# esp32_r1.net
KiCad netlist of a schematic drawn in EAGLE
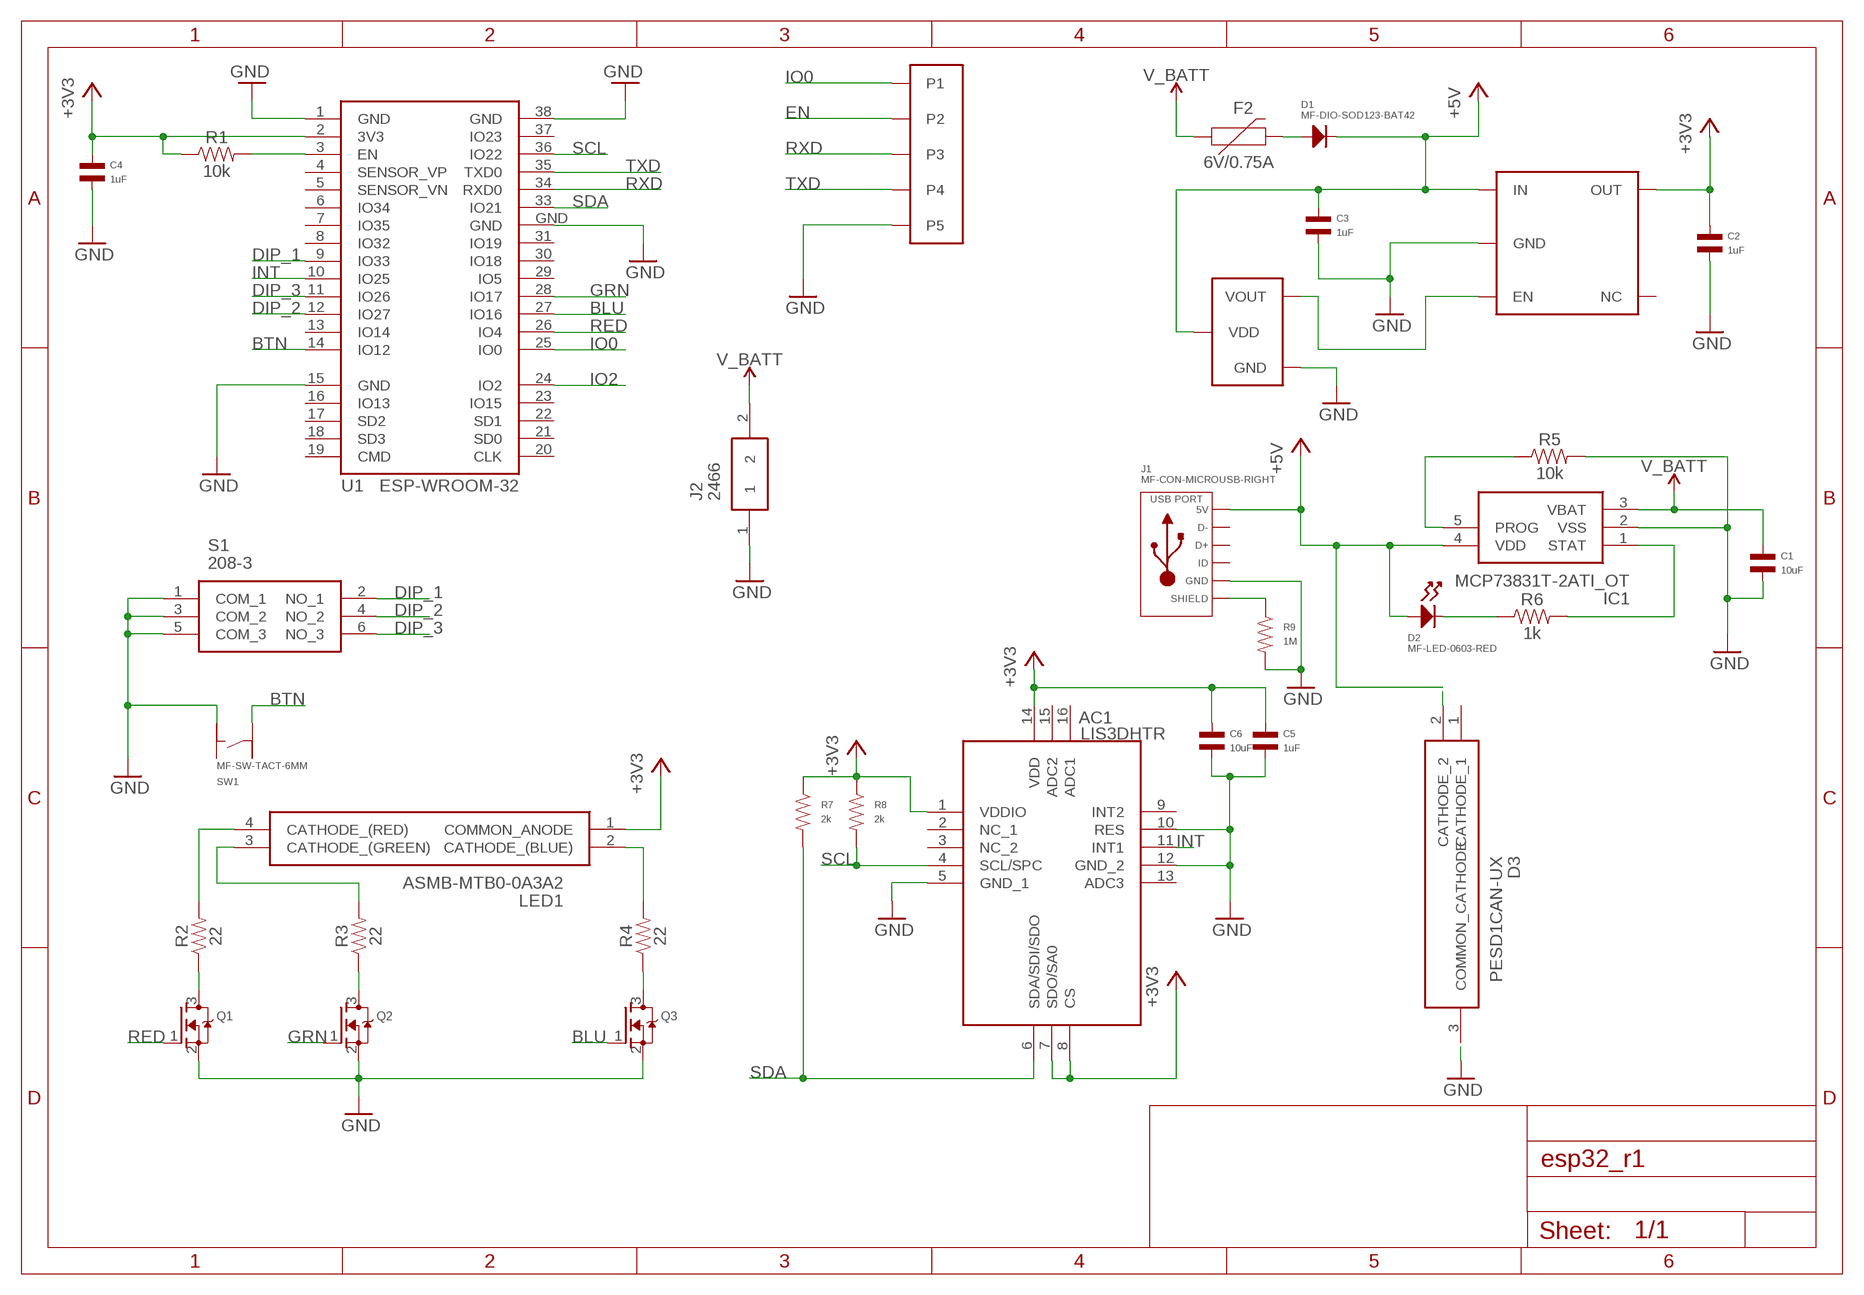
[diagram p0: schematic, sheet 1]

(export (version "E")
  (design (tool "Eeschema 10.0.6"))
  (components
    (comp (ref "AC1")
      (value "LIS3DHTR")
      (footprint "eagle-import:PQFN50P300X300X100-16N")
      (fields (field (name "MOUSER_PART_NUMBER") "511-LIS3DHTR") (field (name "RS_PART_NUMBER") "7931364P"))
      (libsource (lib "eagle-import") (part "LIS3DHTR"))
    )
    (comp (ref "C1")
      (value "10uF")
      (footprint "eagle-import:C1206")
      (libsource (lib "eagle-import") (part "CAPACITOR_NP_1206"))
    )
    (comp (ref "C2")
      (value "1uF")
      (footprint "eagle-import:C0402")
      (libsource (lib "eagle-import") (part "CAPACITOR_NP_0402"))
    )
    (comp (ref "C3")
      (value "1uF")
      (footprint "eagle-import:C0402")
      (libsource (lib "eagle-import") (part "CAPACITOR_NP_0402"))
    )
    (comp (ref "C4")
      (value "1uF")
      (footprint "eagle-import:C0402")
      (libsource (lib "eagle-import") (part "CAPACITOR_NP_0402"))
    )
    (comp (ref "C5")
      (value "1uF")
      (footprint "eagle-import:C0402")
      (libsource (lib "eagle-import") (part "CAPACITOR_NP_0402"))
    )
    (comp (ref "C6")
      (value "10uF")
      (footprint "eagle-import:C1206")
      (libsource (lib "eagle-import") (part "CAPACITOR_NP_1206"))
    )
    (comp (ref "D1")
      (value "MF-DIO-SOD123-BAT42")
      (footprint "eagle-import:SOD-123")
      (fields (field (name "HOUSEPART") "YES"))
      (libsource (lib "eagle-import") (part "DIODES_SOD-123_BAT42"))
    )
    (comp (ref "D2")
      (value "MF-LED-0603-RED")
      (footprint "eagle-import:LED0603")
      (fields (field (name "HOUSEPART") "YES"))
      (libsource (lib "eagle-import") (part "LED_SINGLE-0603-RED"))
    )
    (comp (ref "D3")
      (value "PESD1CAN-UX")
      (footprint "eagle-import:SOT95P230X110-3N")
      (fields (field (name "MOUSER_PART_NUMBER") "771-PESD1CANUX") (field (name "RS_PART_NUMBER") "1362213P"))
      (libsource (lib "eagle-import") (part "PESD1CAN-UX"))
    )
    (comp (ref "F2")
      (value "6V/0.75A")
      (footprint "eagle-import:1206")
      (libsource (lib "eagle-import") (part "PPTC_THREE-QUARTER-AMP"))
    )
    (comp (ref "IC1")
      (value "MCP73831T-2ATI_OT")
      (footprint "eagle-import:SOT95P270X145-5N")
      (fields
        (field (name "MANUFACTURER_PART_NUMBER") "MCP73831T-2ATI/OT")
        (field (name "MOUSER_PART_NUMBER") "579-MCP73831T-2ATIOT")
        (field (name "RS_PART_NUMBER") "7386617P")
      )
      (libsource (lib "eagle-import") (part "MCP73831T-2ATI_OT"))
    )
    (comp (ref "J1")
      (value "MF-CON-MICROUSB-RIGHT")
      (footprint "eagle-import:MICROUSB-RIGHT")
      (fields (field (name "HOUSEPART") "YES"))
      (libsource (lib "eagle-import") (part "USB_MICRO_RIGHT"))
    )
    (comp (ref "J2")
      (value "2466")
      (footprint "eagle-import:2466")
      (fields (field (name "MOUSER_PART_NUMBER") "534-2466"))
      (libsource (lib "eagle-import") (part "2466"))
    )
    (comp (ref "LED1")
      (value "ASMB-MTB0-0A3A2")
      (footprint "eagle-import:AVAGO_PLCC4")
      (fields
        (field (name "MOUSER_PART_NUMBER") "630-ASMB-MTB0-0A3A2")
        (field (name "RS_PART_NUMBER") "8305044P")
      )
      (libsource (lib "eagle-import") (part "ASMB-MTB0-0A3A2"))
    )
    (comp (ref "Q1")
      (value "MOSFET-NREFLOW")
      (footprint "eagle-import:SOT23-R")
      (libsource (lib "eagle-import") (part "MOSFET-NREFLOW"))
    )
    (comp (ref "Q2")
      (value "MOSFET-NREFLOW")
      (footprint "eagle-import:SOT23-R")
      (libsource (lib "eagle-import") (part "MOSFET-NREFLOW"))
    )
    (comp (ref "Q3")
      (value "MOSFET-NREFLOW")
      (footprint "eagle-import:SOT23-R")
      (libsource (lib "eagle-import") (part "MOSFET-NREFLOW"))
    )
    (comp (ref "R1")
      (value "10k")
      (footprint "eagle-import:0402")
      (libsource (lib "eagle-import") (part "100KOHM-0402-1/16W-1%"))
    )
    (comp (ref "R2")
      (value "22")
      (footprint "eagle-import:0402")
      (libsource (lib "eagle-import") (part "22OHM-0402-1/10W-1%"))
    )
    (comp (ref "R3")
      (value "22")
      (footprint "eagle-import:0402")
      (libsource (lib "eagle-import") (part "22OHM-0402-1/10W-1%"))
    )
    (comp (ref "R4")
      (value "22")
      (footprint "eagle-import:0402")
      (libsource (lib "eagle-import") (part "22OHM-0402-1/10W-1%"))
    )
    (comp (ref "R5")
      (value "10k")
      (footprint "eagle-import:0402")
      (libsource (lib "eagle-import") (part "100KOHM-0402-1/16W-1%"))
    )
    (comp (ref "R6")
      (value "1k")
      (footprint "eagle-import:0402")
      (libsource (lib "eagle-import") (part "100KOHM-0402-1/16W-1%"))
    )
    (comp (ref "R7")
      (value "2k")
      (footprint "eagle-import:R0402")
      (libsource (lib "eagle-import") (part "RESISTOR_0402"))
    )
    (comp (ref "R8")
      (value "2k")
      (footprint "eagle-import:R0402")
      (libsource (lib "eagle-import") (part "RESISTOR_0402"))
    )
    (comp (ref "R9")
      (value "1M")
      (footprint "eagle-import:R0402")
      (libsource (lib "eagle-import") (part "RESISTOR_0402"))
    )
    (comp (ref "S1")
      (value "208-3")
      (footprint "eagle-import:2083")
      (fields (field (name "MOUSER_PART_NUMBER") "774-2083") (field (name "RS_PART_NUMBER") "1774319"))
      (libsource (lib "eagle-import") (part "208-3"))
    )
    (comp (ref "SW1")
      (value "MF-SW-TACT-6MM")
      (footprint "eagle-import:TACT6MM")
      (fields (field (name "HOUSEPART") "YES"))
      (libsource (lib "eagle-import") (part "TACT_6MM"))
    )
    (comp (ref "U1")
      (value "ESP-WROOM-32")
      (footprint "eagle-import:ESP-WROOM-32")
      (libsource (lib "eagle-import") (part "ESP-WROOM-32"))
    )
    (comp (ref "U4")
      (value "TLV755")
      (footprint "eagle-import:SOT23-DBV")
      (libsource (lib "eagle-import") (part "TLV755"))
    )
    (comp (ref "U6")
      (value "53047")
      (footprint "eagle-import:PICOBLADE_53047")
      (libsource (lib "eagle-import") (part "53047"))
    )
    (comp (ref "U7")
      (value "BD49K33G")
      (footprint "eagle-import:SSOP3")
      (libsource (lib "eagle-import") (part "BD49K33G"))
    )
  )
  (nets
    (net (code "1") (name "+3V3") (class "Default")
      (node (ref "AC1") (pin "1") (pinfunction "VDDIO_1") (pintype "power_in"))
      (node (ref "AC1") (pin "14") (pinfunction "VDD_14") (pintype "power_in"))
      (node (ref "AC1") (pin "7") (pinfunction "SDO/SA0_7") (pintype "bidirectional"))
      (node (ref "AC1") (pin "8") (pinfunction "CS_8") (pintype "input"))
      (node (ref "C2") (pin "P$1") (pinfunction "P$1_P$1") (pintype "passive"))
      (node (ref "C4") (pin "P$1") (pinfunction "P$1_P$1") (pintype "passive"))
      (node (ref "C5") (pin "P$1") (pinfunction "P$1_P$1") (pintype "passive"))
      (node (ref "C6") (pin "P$1") (pinfunction "P$1_P$1") (pintype "passive"))
      (node (ref "LED1") (pin "1") (pinfunction "COMMON_ANODE_1") (pintype "bidirectional"))
      (node (ref "R1") (pin "1") (pinfunction "1_1") (pintype "passive"))
      (node (ref "R7") (pin "P$1") (pinfunction "P$1_P$1") (pintype "passive"))
      (node (ref "R8") (pin "P$1") (pinfunction "P$1_P$1") (pintype "passive"))
      (node (ref "U1") (pin "2") (pinfunction "3V3_2") (pintype "power_in"))
      (node (ref "U4") (pin "5") (pinfunction "OUT_5") (pintype "bidirectional"))
    )
    (net (code "2") (name "+5V") (class "Default")
      (node (ref "C3") (pin "P$1") (pinfunction "P$1_P$1") (pintype "passive"))
      (node (ref "D1") (pin "CATHODE") (pinfunction "CATHODE_CATHODE") (pintype "bidirectional"))
      (node (ref "D2") (pin "ANODE") (pinfunction "ANODE_ANODE") (pintype "power_in"))
      (node (ref "D3") (pin "2") (pinfunction "CATHODE_2_2") (pintype "bidirectional"))
      (node (ref "IC1") (pin "4") (pinfunction "VDD_4") (pintype "power_in"))
      (node (ref "J1") (pin "1") (pinfunction "5V_1") (pintype "power_in"))
      (node (ref "U4") (pin "1") (pinfunction "IN_1") (pintype "bidirectional"))
      (node (ref "U7") (pin "P$3") (pinfunction "VDD_P$3") (pintype "bidirectional"))
    )
    (net (code "3") (name "/BLU") (class "Default")
      (node (ref "Q3") (pin "1") (pinfunction "G_1") (pintype "bidirectional"))
      (node (ref "U1") (pin "27") (pinfunction "IO16_27") (pintype "bidirectional"))
    )
    (net (code "4") (name "/BTN") (class "Default")
      (node (ref "SW1") (pin "P$4") (pinfunction "P$4_P$4") (pintype "bidirectional"))
      (node (ref "U1") (pin "14") (pinfunction "IO12_14") (pintype "bidirectional"))
    )
    (net (code "5") (name "/DIP_1") (class "Default")
      (node (ref "S1") (pin "2") (pinfunction "NO_1_2") (pintype "bidirectional"))
      (node (ref "U1") (pin "9") (pinfunction "IO33_9") (pintype "bidirectional"))
    )
    (net (code "6") (name "/DIP_2") (class "Default")
      (node (ref "S1") (pin "4") (pinfunction "NO_2_4") (pintype "bidirectional"))
      (node (ref "U1") (pin "12") (pinfunction "IO27_12") (pintype "bidirectional"))
    )
    (net (code "7") (name "/DIP_3") (class "Default")
      (node (ref "S1") (pin "6") (pinfunction "NO_3_6") (pintype "bidirectional"))
      (node (ref "U1") (pin "11") (pinfunction "IO26_11") (pintype "bidirectional"))
    )
    (net (code "8") (name "/EN") (class "Default")
      (node (ref "R1") (pin "2") (pinfunction "2_2") (pintype "passive"))
      (node (ref "U1") (pin "3") (pinfunction "EN_3") (pintype "input"))
      (node (ref "U6") (pin "P$2") (pinfunction "P2_P$2") (pintype "bidirectional"))
    )
    (net (code "9") (name "/GRN") (class "Default")
      (node (ref "Q2") (pin "1") (pinfunction "G_1") (pintype "bidirectional"))
      (node (ref "U1") (pin "28") (pinfunction "IO17_28") (pintype "bidirectional"))
    )
    (net (code "10") (name "/INT") (class "Default")
      (node (ref "AC1") (pin "11") (pinfunction "INT1_11") (pintype "input"))
      (node (ref "U1") (pin "10") (pinfunction "IO25_10") (pintype "bidirectional"))
    )
    (net (code "11") (name "/IO0") (class "Default")
      (node (ref "U1") (pin "25") (pinfunction "IO0_25") (pintype "bidirectional"))
      (node (ref "U6") (pin "P$1") (pinfunction "P1_P$1") (pintype "bidirectional"))
    )
    (net (code "12") (name "/IO2") (class "Default")
      (node (ref "U1") (pin "24") (pinfunction "IO2_24") (pintype "bidirectional"))
    )
    (net (code "13") (name "/RED") (class "Default")
      (node (ref "Q1") (pin "1") (pinfunction "G_1") (pintype "bidirectional"))
      (node (ref "U1") (pin "26") (pinfunction "IO4_26") (pintype "bidirectional"))
    )
    (net (code "14") (name "/RXD") (class "Default")
      (node (ref "U1") (pin "34") (pinfunction "RXD0_34") (pintype "bidirectional"))
      (node (ref "U6") (pin "P$3") (pinfunction "P3_P$3") (pintype "bidirectional"))
    )
    (net (code "15") (name "/SCL") (class "Default")
      (node (ref "AC1") (pin "4") (pinfunction "SCL/SPC_4") (pintype "bidirectional"))
      (node (ref "R8") (pin "P$2") (pinfunction "P$2_P$2") (pintype "passive"))
      (node (ref "U1") (pin "36") (pinfunction "IO22_36") (pintype "bidirectional"))
    )
    (net (code "16") (name "/SDA") (class "Default")
      (node (ref "AC1") (pin "6") (pinfunction "SDA/SDI/SDO_6") (pintype "bidirectional"))
      (node (ref "R7") (pin "P$2") (pinfunction "P$2_P$2") (pintype "passive"))
      (node (ref "U1") (pin "33") (pinfunction "IO21_33") (pintype "bidirectional"))
    )
    (net (code "17") (name "/TXD") (class "Default")
      (node (ref "U1") (pin "35") (pinfunction "TXD0_35") (pintype "bidirectional"))
      (node (ref "U6") (pin "P$4") (pinfunction "P4_P$4") (pintype "bidirectional"))
    )
    (net (code "18") (name "GND") (class "Default")
      (node (ref "AC1") (pin "10") (pinfunction "RES_10") (pintype "bidirectional"))
      (node (ref "AC1") (pin "12") (pinfunction "GND_2_12") (pintype "power_in"))
      (node (ref "AC1") (pin "5") (pinfunction "GND_1_5") (pintype "power_in"))
      (node (ref "C1") (pin "P$2") (pinfunction "P$2_P$2") (pintype "passive"))
      (node (ref "C2") (pin "P$2") (pinfunction "P$2_P$2") (pintype "passive"))
      (node (ref "C3") (pin "P$2") (pinfunction "P$2_P$2") (pintype "passive"))
      (node (ref "C4") (pin "P$2") (pinfunction "P$2_P$2") (pintype "passive"))
      (node (ref "C5") (pin "P$2") (pinfunction "P$2_P$2") (pintype "passive"))
      (node (ref "C6") (pin "P$2") (pinfunction "P$2_P$2") (pintype "passive"))
      (node (ref "D3") (pin "3") (pinfunction "COMMON_CATHODE_3") (pintype "bidirectional"))
      (node (ref "IC1") (pin "2") (pinfunction "VSS_2") (pintype "power_in"))
      (node (ref "J1") (pin "5") (pinfunction "GND_5") (pintype "power_in"))
      (node (ref "J2") (pin "1") (pinfunction "1_1") (pintype "bidirectional"))
      (node (ref "Q1") (pin "2") (pinfunction "S_2") (pintype "bidirectional"))
      (node (ref "Q2") (pin "2") (pinfunction "S_2") (pintype "bidirectional"))
      (node (ref "Q3") (pin "2") (pinfunction "S_2") (pintype "bidirectional"))
      (node (ref "R5") (pin "2") (pinfunction "2_2") (pintype "passive"))
      (node (ref "R9") (pin "P$2") (pinfunction "P$2_P$2") (pintype "passive"))
      (node (ref "S1") (pin "1") (pinfunction "COM_1_1") (pintype "bidirectional"))
      (node (ref "S1") (pin "3") (pinfunction "COM_2_3") (pintype "bidirectional"))
      (node (ref "S1") (pin "5") (pinfunction "COM_3_5") (pintype "bidirectional"))
      (node (ref "SW1") (pin "P$2") (pinfunction "P$2_P$2") (pintype "bidirectional"))
      (node (ref "U1") (pin "1") (pinfunction "GND_1") (pintype "power_in"))
      (node (ref "U1") (pin "15") (pinfunction "GND_15") (pintype "power_in"))
      (node (ref "U1") (pin "38") (pinfunction "GND_38") (pintype "power_in"))
      (node (ref "U1") (pin "GND") (pinfunction "GND_GND") (pintype "power_in"))
      (node (ref "U4") (pin "2") (pinfunction "GND_2") (pintype "bidirectional"))
      (node (ref "U6") (pin "P$5") (pinfunction "P5_P$5") (pintype "bidirectional"))
      (node (ref "U7") (pin "P$1") (pinfunction "GND_P$1") (pintype "bidirectional"))
    )
    (net (code "19") (name "Net-(D1-PadANODE)") (class "Default")
      (node (ref "D1") (pin "ANODE") (pinfunction "ANODE_ANODE") (pintype "bidirectional"))
      (node (ref "F2") (pin "2") (pinfunction "2_2") (pintype "bidirectional"))
    )
    (net (code "20") (name "Net-(D2-PadCATHODE)") (class "Default")
      (node (ref "D2") (pin "CATHODE") (pinfunction "CATHODE_CATHODE") (pintype "power_in"))
      (node (ref "R6") (pin "1") (pinfunction "1_1") (pintype "passive"))
    )
    (net (code "21") (name "Net-(IC1-PROG)") (class "Default")
      (node (ref "IC1") (pin "5") (pinfunction "PROG_5") (pintype "bidirectional"))
      (node (ref "R5") (pin "1") (pinfunction "1_1") (pintype "passive"))
    )
    (net (code "22") (name "Net-(IC1-STAT)") (class "Default")
      (node (ref "IC1") (pin "1") (pinfunction "STAT_1") (pintype "bidirectional"))
      (node (ref "R6") (pin "2") (pinfunction "2_2") (pintype "passive"))
    )
    (net (code "23") (name "Net-(J1-SLD-PadS1)") (class "Default")
      (node (ref "J1") (pin "S1") (pinfunction "SLD_S1") (pintype "power_in"))
      (node (ref "J1") (pin "S2") (pinfunction "SLD_S2") (pintype "power_in"))
      (node (ref "J1") (pin "S3") (pinfunction "SLD_S3") (pintype "power_in"))
      (node (ref "J1") (pin "S4") (pinfunction "SLD_S4") (pintype "power_in"))
      (node (ref "J1") (pin "S5") (pinfunction "SLD_S5") (pintype "power_in"))
      (node (ref "J1") (pin "S6") (pinfunction "SLD_S6") (pintype "power_in"))
      (node (ref "R9") (pin "P$1") (pinfunction "P$1_P$1") (pintype "passive"))
    )
    (net (code "24") (name "Net-(LED1-CATHODE_(BLUE))") (class "Default")
      (node (ref "LED1") (pin "2") (pinfunction "CATHODE_(BLUE)_2") (pintype "bidirectional"))
      (node (ref "R4") (pin "2") (pinfunction "2_2") (pintype "passive"))
    )
    (net (code "25") (name "Net-(LED1-CATHODE_(GREEN))") (class "Default")
      (node (ref "LED1") (pin "3") (pinfunction "CATHODE_(GREEN)_3") (pintype "bidirectional"))
      (node (ref "R3") (pin "2") (pinfunction "2_2") (pintype "passive"))
    )
    (net (code "26") (name "Net-(LED1-CATHODE_(RED))") (class "Default")
      (node (ref "LED1") (pin "4") (pinfunction "CATHODE_(RED)_4") (pintype "bidirectional"))
      (node (ref "R2") (pin "2") (pinfunction "2_2") (pintype "passive"))
    )
    (net (code "27") (name "Net-(Q1-D)") (class "Default")
      (node (ref "Q1") (pin "3") (pinfunction "D_3") (pintype "bidirectional"))
      (node (ref "R2") (pin "1") (pinfunction "1_1") (pintype "passive"))
    )
    (net (code "28") (name "Net-(Q2-D)") (class "Default")
      (node (ref "Q2") (pin "3") (pinfunction "D_3") (pintype "bidirectional"))
      (node (ref "R3") (pin "1") (pinfunction "1_1") (pintype "passive"))
    )
    (net (code "29") (name "Net-(Q3-D)") (class "Default")
      (node (ref "Q3") (pin "3") (pinfunction "D_3") (pintype "bidirectional"))
      (node (ref "R4") (pin "1") (pinfunction "1_1") (pintype "passive"))
    )
    (net (code "30") (name "Net-(U4-EN)") (class "Default")
      (node (ref "U4") (pin "3") (pinfunction "EN_3") (pintype "bidirectional"))
      (node (ref "U7") (pin "P$2") (pinfunction "VOUT_P$2") (pintype "bidirectional"))
    )
    (net (code "31") (name "V_BATT") (class "Default")
      (node (ref "C1") (pin "P$1") (pinfunction "P$1_P$1") (pintype "passive"))
      (node (ref "F2") (pin "1") (pinfunction "1_1") (pintype "bidirectional"))
      (node (ref "IC1") (pin "3") (pinfunction "VBAT_3") (pintype "bidirectional"))
      (node (ref "J2") (pin "2") (pinfunction "2_2") (pintype "bidirectional"))
    )
    (net (code "32") (name "unconnected-(AC1-ADC1-Pad16)") (class "Default")
      (node (ref "AC1") (pin "16") (pinfunction "ADC1_16") (pintype "bidirectional"))
    )
    (net (code "33") (name "unconnected-(AC1-ADC2-Pad15)") (class "Default")
      (node (ref "AC1") (pin "15") (pinfunction "ADC2_15") (pintype "bidirectional"))
    )
    (net (code "34") (name "unconnected-(AC1-ADC3-Pad13)") (class "Default")
      (node (ref "AC1") (pin "13") (pinfunction "ADC3_13") (pintype "bidirectional"))
    )
    (net (code "35") (name "unconnected-(AC1-INT2-Pad9)") (class "Default")
      (node (ref "AC1") (pin "9") (pinfunction "INT2_9") (pintype "input"))
    )
    (net (code "36") (name "unconnected-(AC1-NC_1-Pad2)") (class "Default")
      (node (ref "AC1") (pin "2") (pinfunction "NC_1_2") (pintype "bidirectional"))
    )
    (net (code "37") (name "unconnected-(AC1-NC_2-Pad3)") (class "Default")
      (node (ref "AC1") (pin "3") (pinfunction "NC_2_3") (pintype "bidirectional"))
    )
    (net (code "38") (name "unconnected-(D3-CATHODE_1-Pad1)") (class "Default")
      (node (ref "D3") (pin "1") (pinfunction "CATHODE_1_1") (pintype "bidirectional"))
    )
    (net (code "39") (name "unconnected-(J1-D+-Pad3)") (class "Default")
      (node (ref "J1") (pin "3") (pinfunction "D+_3") (pintype "bidirectional"))
    )
    (net (code "40") (name "unconnected-(J1-D--Pad2)") (class "Default")
      (node (ref "J1") (pin "2") (pinfunction "D-_2") (pintype "bidirectional"))
    )
    (net (code "41") (name "unconnected-(J1-ID-Pad4)") (class "Default")
      (node (ref "J1") (pin "4") (pinfunction "ID_4") (pintype "bidirectional"))
    )
    (net (code "42") (name "unconnected-(SW1-PadP$1)") (class "Default")
      (node (ref "SW1") (pin "P$1") (pinfunction "P$1_P$1") (pintype "bidirectional"))
    )
    (net (code "43") (name "unconnected-(SW1-PadP$3)") (class "Default")
      (node (ref "SW1") (pin "P$3") (pinfunction "P$3_P$3") (pintype "bidirectional"))
    )
    (net (code "44") (name "unconnected-(U1-CLK-Pad20)") (class "Default")
      (node (ref "U1") (pin "20") (pinfunction "CLK_20") (pintype "bidirectional"))
    )
    (net (code "45") (name "unconnected-(U1-CMD-Pad19)") (class "Default")
      (node (ref "U1") (pin "19") (pinfunction "CMD_19") (pintype "bidirectional"))
    )
    (net (code "46") (name "unconnected-(U1-IO5-Pad29)") (class "Default")
      (node (ref "U1") (pin "29") (pinfunction "IO5_29") (pintype "bidirectional"))
    )
    (net (code "47") (name "unconnected-(U1-IO13-Pad16)") (class "Default")
      (node (ref "U1") (pin "16") (pinfunction "IO13_16") (pintype "bidirectional"))
    )
    (net (code "48") (name "unconnected-(U1-IO14-Pad13)") (class "Default")
      (node (ref "U1") (pin "13") (pinfunction "IO14_13") (pintype "bidirectional"))
    )
    (net (code "49") (name "unconnected-(U1-IO15-Pad23)") (class "Default")
      (node (ref "U1") (pin "23") (pinfunction "IO15_23") (pintype "bidirectional"))
    )
    (net (code "50") (name "unconnected-(U1-IO18-Pad30)") (class "Default")
      (node (ref "U1") (pin "30") (pinfunction "IO18_30") (pintype "bidirectional"))
    )
    (net (code "51") (name "unconnected-(U1-IO19-Pad31)") (class "Default")
      (node (ref "U1") (pin "31") (pinfunction "IO19_31") (pintype "bidirectional"))
    )
    (net (code "52") (name "unconnected-(U1-IO23-Pad37)") (class "Default")
      (node (ref "U1") (pin "37") (pinfunction "IO23_37") (pintype "bidirectional"))
    )
    (net (code "53") (name "unconnected-(U1-IO32-Pad8)") (class "Default")
      (node (ref "U1") (pin "8") (pinfunction "IO32_8") (pintype "bidirectional"))
    )
    (net (code "54") (name "unconnected-(U1-IO34-Pad6)") (class "Default")
      (node (ref "U1") (pin "6") (pinfunction "IO34_6") (pintype "bidirectional"))
    )
    (net (code "55") (name "unconnected-(U1-IO35-Pad7)") (class "Default")
      (node (ref "U1") (pin "7") (pinfunction "IO35_7") (pintype "bidirectional"))
    )
    (net (code "56") (name "unconnected-(U1-SD0-Pad21)") (class "Default")
      (node (ref "U1") (pin "21") (pinfunction "SD0_21") (pintype "bidirectional"))
    )
    (net (code "57") (name "unconnected-(U1-SD1-Pad22)") (class "Default")
      (node (ref "U1") (pin "22") (pinfunction "SD1_22") (pintype "bidirectional"))
    )
    (net (code "58") (name "unconnected-(U1-SD2-Pad17)") (class "Default")
      (node (ref "U1") (pin "17") (pinfunction "SD2_17") (pintype "bidirectional"))
    )
    (net (code "59") (name "unconnected-(U1-SD3-Pad18)") (class "Default")
      (node (ref "U1") (pin "18") (pinfunction "SD3_18") (pintype "bidirectional"))
    )
    (net (code "60") (name "unconnected-(U1-SENSOR_VN-Pad5)") (class "Default")
      (node (ref "U1") (pin "5") (pinfunction "SENSOR_VN_5") (pintype "bidirectional"))
    )
    (net (code "61") (name "unconnected-(U1-SENSOR_VP-Pad4)") (class "Default")
      (node (ref "U1") (pin "4") (pinfunction "SENSOR_VP_4") (pintype "bidirectional"))
    )
    (net (code "62") (name "unconnected-(U4-NC-Pad4)") (class "Default")
      (node (ref "U4") (pin "4") (pinfunction "NC_4") (pintype "bidirectional"))
    )
  )
)
